# Top.net
KiCad netlist of a schematic drawn in Altium Designer
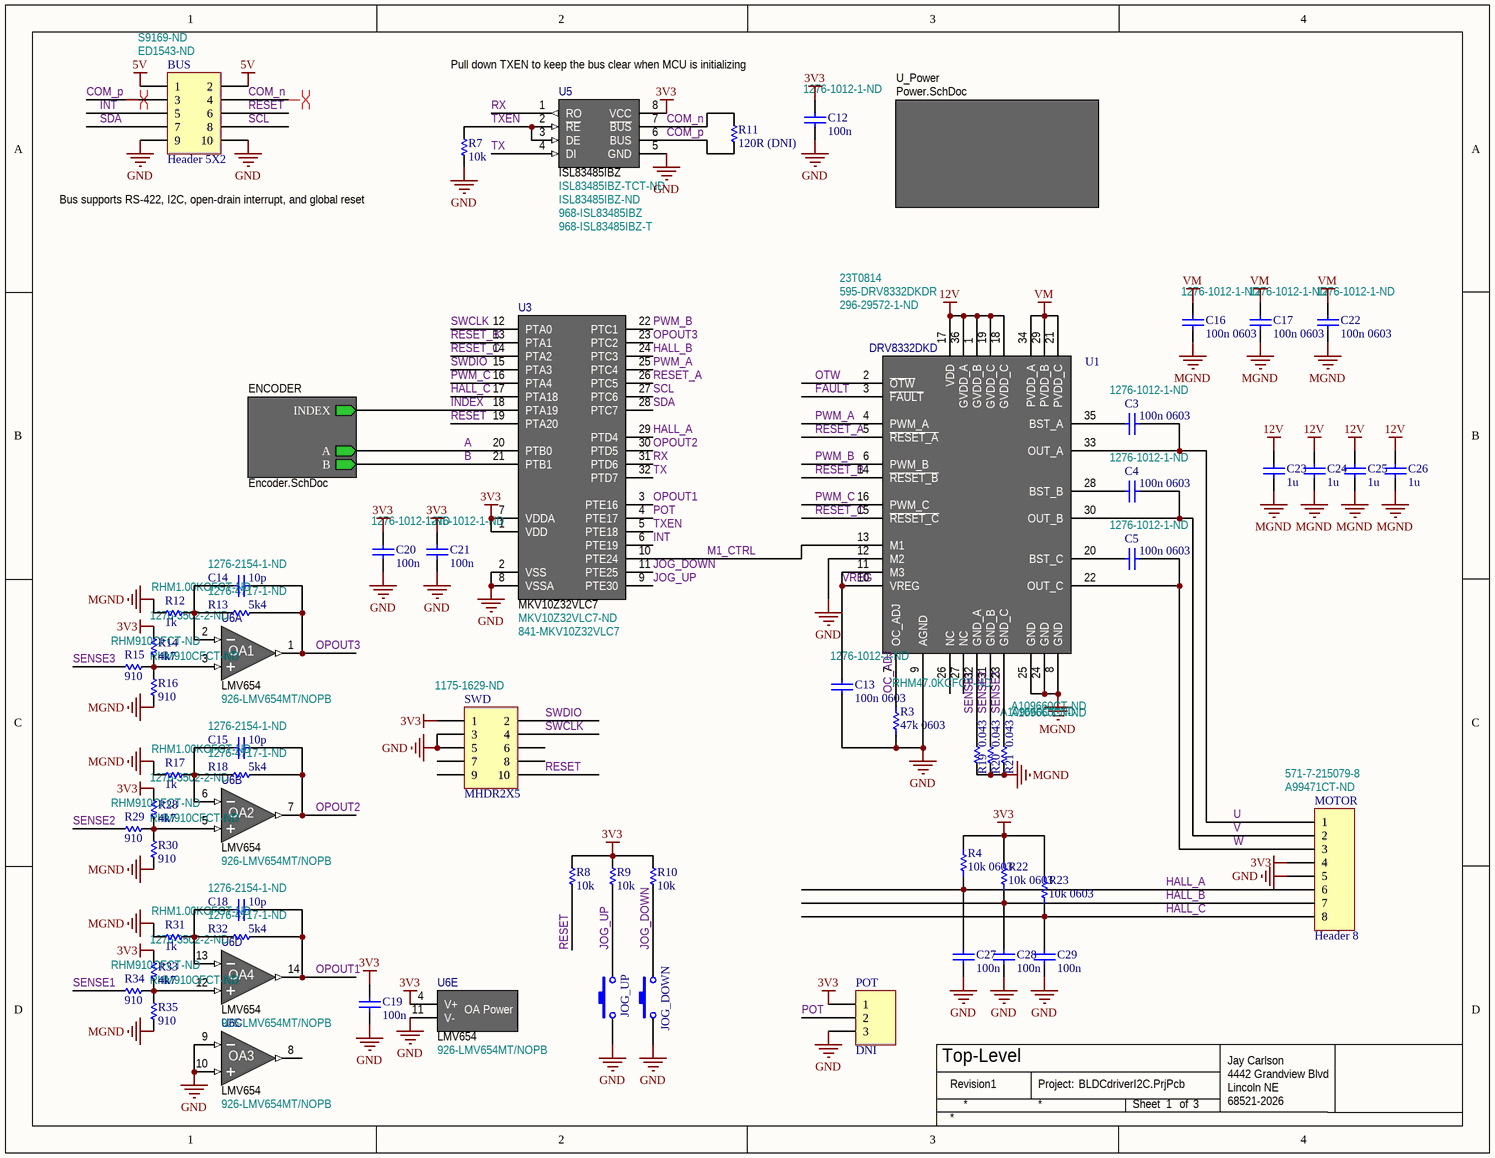
[diagram p0: Top.SchDoc]

(export (version "E")
  (design (tool "Eeschema 10.0.6"))
  (components
    (comp (ref "BUS")
      (value "Header 5X2")
      (footprint "HDR2X5_SHROUDED")
      (description "Header, 5-Pin, Dual row")
      (fields
        (field (name "SUPPLIER PART NUMBER 1") "ED1543-ND")
        (field (name "SUPPLIER PART NUMBER 2") "S9169-ND")
        (field (name "PUBLISHER") "Altium Limited")
      )
      (libsource (lib "Miscellaneous Connectors") (part "Header 5X2"))
    )
    (comp (ref "C3")
      (value "100n 0603")
      (footprint "CAPC1608N")
      (description "Capacitor")
      (fields
        (field (name "SUPPLIER PART NUMBER 1") "1276-1012-1-ND")
        (field (name "PUBLISHER") "Altium Limited")
      )
      (libsource (lib "Miscellaneous Devices") (part "Cap"))
    )
    (comp (ref "C4")
      (value "100n 0603")
      (footprint "CAPC1608N")
      (description "Capacitor")
      (fields
        (field (name "SUPPLIER PART NUMBER 1") "1276-1012-1-ND")
        (field (name "PUBLISHER") "Altium Limited")
      )
      (libsource (lib "Miscellaneous Devices") (part "Cap"))
    )
    (comp (ref "C5")
      (value "100n 0603")
      (footprint "CAPC1608N")
      (description "Capacitor")
      (fields
        (field (name "SUPPLIER PART NUMBER 1") "1276-1012-1-ND")
        (field (name "PUBLISHER") "Altium Limited")
      )
      (libsource (lib "Miscellaneous Devices") (part "Cap"))
    )
    (comp (ref "C12")
      (value "100n")
      (footprint "CAPC1608N")
      (description "Capacitor (Semiconductor SIM Model)")
      (fields
        (field (name "SUPPLIER PART NUMBER 1") "1276-1012-1-ND")
        (field (name "PUBLISHER") "Altium Limited")
      )
      (libsource (lib "Miscellaneous Devices") (part "Cap Semi"))
    )
    (comp (ref "C13")
      (value "100n 0603")
      (footprint "CAPC1608N")
      (description "Capacitor")
      (fields
        (field (name "SUPPLIER PART NUMBER 1") "1276-1012-1-ND")
        (field (name "PUBLISHER") "Altium Limited")
      )
      (libsource (lib "Miscellaneous Devices") (part "Cap"))
    )
    (comp (ref "C14")
      (value "10p")
      (footprint "CAPC1608N")
      (description "Capacitor (Semiconductor SIM Model)")
      (fields
        (field (name "SUPPLIER PART NUMBER 1") "1276-2154-1-ND")
        (field (name "PUBLISHER") "Altium Limited")
      )
      (libsource (lib "Miscellaneous Devices") (part "Cap Semi"))
    )
    (comp (ref "C15")
      (value "10p")
      (footprint "CAPC1608N")
      (description "Capacitor (Semiconductor SIM Model)")
      (fields
        (field (name "SUPPLIER PART NUMBER 1") "1276-2154-1-ND")
        (field (name "PUBLISHER") "Altium Limited")
      )
      (libsource (lib "Miscellaneous Devices") (part "Cap Semi"))
    )
    (comp (ref "C16")
      (value "100n 0603")
      (footprint "CAPC1608N")
      (description "Capacitor")
      (fields
        (field (name "SUPPLIER PART NUMBER 1") "1276-1012-1-ND")
        (field (name "PUBLISHER") "Altium Limited")
      )
      (libsource (lib "Miscellaneous Devices") (part "Cap"))
    )
    (comp (ref "C17")
      (value "100n 0603")
      (footprint "CAPC1608N")
      (description "Capacitor")
      (fields
        (field (name "SUPPLIER PART NUMBER 1") "1276-1012-1-ND")
        (field (name "PUBLISHER") "Altium Limited")
      )
      (libsource (lib "Miscellaneous Devices") (part "Cap"))
    )
    (comp (ref "C18")
      (value "10p")
      (footprint "CAPC1608N")
      (description "Capacitor (Semiconductor SIM Model)")
      (fields
        (field (name "SUPPLIER PART NUMBER 1") "1276-2154-1-ND")
        (field (name "PUBLISHER") "Altium Limited")
      )
      (libsource (lib "Miscellaneous Devices") (part "Cap Semi"))
    )
    (comp (ref "C19")
      (value "100n")
      (footprint "CAPC1608N")
      (description "Capacitor (Semiconductor SIM Model)")
      (fields (field (name "PUBLISHER") "Altium Limited"))
      (libsource (lib "Miscellaneous Devices") (part "Cap Semi"))
    )
    (comp (ref "C20")
      (value "100n")
      (footprint "CAPC1608N")
      (description "Capacitor (Semiconductor SIM Model)")
      (fields
        (field (name "SUPPLIER PART NUMBER 1") "1276-1012-1-ND")
        (field (name "PUBLISHER") "Altium Limited")
      )
      (libsource (lib "Miscellaneous Devices") (part "Cap Semi"))
    )
    (comp (ref "C21")
      (value "100n")
      (footprint "CAPC1608N")
      (description "Capacitor (Semiconductor SIM Model)")
      (fields
        (field (name "SUPPLIER PART NUMBER 1") "1276-1012-1-ND")
        (field (name "PUBLISHER") "Altium Limited")
      )
      (libsource (lib "Miscellaneous Devices") (part "Cap Semi"))
    )
    (comp (ref "C22")
      (value "100n 0603")
      (footprint "CAPC1608N")
      (description "Capacitor")
      (fields
        (field (name "SUPPLIER PART NUMBER 1") "1276-1012-1-ND")
        (field (name "PUBLISHER") "Altium Limited")
      )
      (libsource (lib "Miscellaneous Devices") (part "Cap"))
    )
    (comp (ref "C23")
      (value "1u")
      (footprint "CAPC1608N")
      (description "Capacitor (Semiconductor SIM Model)")
      (fields (field (name "PUBLISHER") "Altium Limited"))
      (libsource (lib "Miscellaneous Devices") (part "Cap Semi"))
    )
    (comp (ref "C24")
      (value "1u")
      (footprint "CAPC1608N")
      (description "Capacitor (Semiconductor SIM Model)")
      (fields (field (name "PUBLISHER") "Altium Limited"))
      (libsource (lib "Miscellaneous Devices") (part "Cap Semi"))
    )
    (comp (ref "C25")
      (value "1u")
      (footprint "CAPC1608N")
      (description "Capacitor (Semiconductor SIM Model)")
      (fields (field (name "PUBLISHER") "Altium Limited"))
      (libsource (lib "Miscellaneous Devices") (part "Cap Semi"))
    )
    (comp (ref "C26")
      (value "1u")
      (footprint "CAPC1608N")
      (description "Capacitor (Semiconductor SIM Model)")
      (fields (field (name "PUBLISHER") "Altium Limited"))
      (libsource (lib "Miscellaneous Devices") (part "Cap Semi"))
    )
    (comp (ref "C27")
      (value "100n")
      (footprint "CAPC1608N")
      (description "Capacitor (Semiconductor SIM Model)")
      (fields (field (name "PUBLISHER") "Altium Limited"))
      (libsource (lib "Miscellaneous Devices") (part "Cap Semi"))
    )
    (comp (ref "C28")
      (value "100n")
      (footprint "CAPC1608N")
      (description "Capacitor (Semiconductor SIM Model)")
      (fields (field (name "PUBLISHER") "Altium Limited"))
      (libsource (lib "Miscellaneous Devices") (part "Cap Semi"))
    )
    (comp (ref "C29")
      (value "100n")
      (footprint "CAPC1608N")
      (description "Capacitor (Semiconductor SIM Model)")
      (fields (field (name "PUBLISHER") "Altium Limited"))
      (libsource (lib "Miscellaneous Devices") (part "Cap Semi"))
    )
    (comp (ref "JOG_DOWN")
      (value "SW-PB")
      (footprint "SW/PB-SMD/H8")
      (description "Switch")
      (fields (field (name "PUBLISHER") "Altium Limited"))
      (libsource (lib "Miscellaneous Devices") (part "SW-PB"))
    )
    (comp (ref "JOG_UP")
      (value "SW-PB")
      (footprint "SW/PB-SMD/H8")
      (description "Switch")
      (fields (field (name "PUBLISHER") "Altium Limited"))
      (libsource (lib "Miscellaneous Devices") (part "SW-PB"))
    )
    (comp (ref "MOTOR")
      (value "Header 8")
      (footprint "7-215079-8")
      (description "Header, 8-Pin")
      (fields
        (field (name "SUPPLIER PART NUMBER 1") "A99471CT-ND")
        (field (name "SUPPLIER PART NUMBER 2") "571-7-215079-8")
        (field (name "PUBLISHER") "Altium Limited")
      )
      (libsource (lib "Miscellaneous Connectors") (part "Header 8"))
    )
    (comp (ref "POT")
      (value "DNI")
      (footprint "HDR1X3")
      (description "Header, 3-Pin")
      (fields (field (name "PUBLISHER") "Altium Limited"))
      (libsource (lib "Miscellaneous Connectors") (part "Header 3"))
    )
    (comp (ref "R3")
      (value "47k 0603")
      (footprint "RESC1608N")
      (description "Semiconductor Resistor")
      (fields
        (field (name "SUPPLIER PART NUMBER 1") "RHM47.0KCFCT-ND")
        (field (name "PUBLISHER") "Altium Limited")
      )
      (libsource (lib "") (part "Res Semi_1"))
    )
    (comp (ref "R4")
      (value "10k 0603")
      (footprint "RESC1608N")
      (description "Semiconductor Resistor")
      (fields (field (name "PUBLISHER") "Altium Limited"))
      (libsource (lib "") (part "Res Semi_1"))
    )
    (comp (ref "R7")
      (value "10k")
      (footprint "RESC1608N")
      (description "Semiconductor Resistor")
      (fields (field (name "PUBLISHER") "Altium Limited"))
      (libsource (lib "Miscellaneous Devices") (part "Res Semi"))
    )
    (comp (ref "R8")
      (value "10k")
      (footprint "RESC1608N")
      (description "Semiconductor Resistor")
      (fields (field (name "PUBLISHER") "Altium Limited"))
      (libsource (lib "Miscellaneous Devices") (part "Res Semi"))
    )
    (comp (ref "R9")
      (value "10k")
      (footprint "RESC1608N")
      (description "Semiconductor Resistor")
      (fields (field (name "PUBLISHER") "Altium Limited"))
      (libsource (lib "Miscellaneous Devices") (part "Res Semi"))
    )
    (comp (ref "R10")
      (value "10k")
      (footprint "RESC1608N")
      (description "Semiconductor Resistor")
      (fields (field (name "PUBLISHER") "Altium Limited"))
      (libsource (lib "Miscellaneous Devices") (part "Res Semi"))
    )
    (comp (ref "R11")
      (value "120R (DNI)")
      (footprint "RESC1608N")
      (description "Semiconductor Resistor")
      (fields (field (name "PUBLISHER") "Altium Limited"))
      (libsource (lib "Miscellaneous Devices") (part "Res Semi"))
    )
    (comp (ref "R12")
      (value "1k")
      (footprint "RESC1608N")
      (description "Semiconductor Resistor")
      (fields
        (field (name "SUPPLIER PART NUMBER 1") "RHM1.00KCFCT-ND")
        (field (name "PUBLISHER") "Altium Limited")
      )
      (libsource (lib "Miscellaneous Devices") (part "Res Semi"))
    )
    (comp (ref "R13")
      (value "5k4")
      (footprint "RESC1608N")
      (description "Semiconductor Resistor")
      (fields
        (field (name "SUPPLIER PART NUMBER 1") "1276-4717-1-ND")
        (field (name "PUBLISHER") "Altium Limited")
      )
      (libsource (lib "Miscellaneous Devices") (part "Res Semi"))
    )
    (comp (ref "R14")
      (value "4k7")
      (footprint "RESC1608N")
      (description "Semiconductor Resistor")
      (fields
        (field (name "SUPPLIER PART NUMBER 1") "1276-3502-2-ND")
        (field (name "PUBLISHER") "Altium Limited")
      )
      (libsource (lib "Miscellaneous Devices") (part "Res Semi"))
    )
    (comp (ref "R15")
      (value "910")
      (footprint "RESC1608N")
      (description "Semiconductor Resistor")
      (fields
        (field (name "SUPPLIER PART NUMBER 1") "RHM910CFCT-ND")
        (field (name "PUBLISHER") "Altium Limited")
      )
      (libsource (lib "Miscellaneous Devices") (part "Res Semi"))
    )
    (comp (ref "R16")
      (value "910")
      (footprint "RESC1608N")
      (description "Semiconductor Resistor")
      (fields
        (field (name "SUPPLIER PART NUMBER 1") "RHM910CFCT-ND")
        (field (name "PUBLISHER") "Altium Limited")
      )
      (libsource (lib "Miscellaneous Devices") (part "Res Semi"))
    )
    (comp (ref "R17")
      (value "1k")
      (footprint "RESC1608N")
      (description "Semiconductor Resistor")
      (fields
        (field (name "SUPPLIER PART NUMBER 1") "RHM1.00KCFCT-ND")
        (field (name "PUBLISHER") "Altium Limited")
      )
      (libsource (lib "Miscellaneous Devices") (part "Res Semi"))
    )
    (comp (ref "R18")
      (value "5k4")
      (footprint "RESC1608N")
      (description "Semiconductor Resistor")
      (fields
        (field (name "SUPPLIER PART NUMBER 1") "1276-4717-1-ND")
        (field (name "PUBLISHER") "Altium Limited")
      )
      (libsource (lib "Miscellaneous Devices") (part "Res Semi"))
    )
    (comp (ref "R19")
      (value "0.043")
      (footprint "RESC3216N")
      (description "Semiconductor Resistor")
      (fields
        (field (name "SUPPLIER PART NUMBER 1") "A109660CT-ND")
        (field (name "PUBLISHER") "Altium Limited")
      )
      (libsource (lib "Miscellaneous Devices") (part "Res Semi"))
    )
    (comp (ref "R20")
      (value "0.043")
      (footprint "RESC3216N")
      (description "Semiconductor Resistor")
      (fields
        (field (name "SUPPLIER PART NUMBER 1") "A109660CT-ND")
        (field (name "PUBLISHER") "Altium Limited")
      )
      (libsource (lib "Miscellaneous Devices") (part "Res Semi"))
    )
    (comp (ref "R21")
      (value "0.043")
      (footprint "RESC3216N")
      (description "Semiconductor Resistor")
      (fields
        (field (name "SUPPLIER PART NUMBER 1") "A109660CT-ND")
        (field (name "PUBLISHER") "Altium Limited")
      )
      (libsource (lib "Miscellaneous Devices") (part "Res Semi"))
    )
    (comp (ref "R22")
      (value "10k 0603")
      (footprint "RESC1608N")
      (description "Semiconductor Resistor")
      (fields (field (name "PUBLISHER") "Altium Limited"))
      (libsource (lib "") (part "Res Semi_1"))
    )
    (comp (ref "R23")
      (value "10k 0603")
      (footprint "RESC1608N")
      (description "Semiconductor Resistor")
      (fields (field (name "PUBLISHER") "Altium Limited"))
      (libsource (lib "") (part "Res Semi_1"))
    )
    (comp (ref "R28")
      (value "4k7")
      (footprint "RESC1608N")
      (description "Semiconductor Resistor")
      (fields
        (field (name "SUPPLIER PART NUMBER 1") "1276-3502-2-ND")
        (field (name "PUBLISHER") "Altium Limited")
      )
      (libsource (lib "Miscellaneous Devices") (part "Res Semi"))
    )
    (comp (ref "R29")
      (value "910")
      (footprint "RESC1608N")
      (description "Semiconductor Resistor")
      (fields
        (field (name "SUPPLIER PART NUMBER 1") "RHM910CFCT-ND")
        (field (name "PUBLISHER") "Altium Limited")
      )
      (libsource (lib "Miscellaneous Devices") (part "Res Semi"))
    )
    (comp (ref "R30")
      (value "910")
      (footprint "RESC1608N")
      (description "Semiconductor Resistor")
      (fields
        (field (name "SUPPLIER PART NUMBER 1") "RHM910CFCT-ND")
        (field (name "PUBLISHER") "Altium Limited")
      )
      (libsource (lib "Miscellaneous Devices") (part "Res Semi"))
    )
    (comp (ref "R31")
      (value "1k")
      (footprint "RESC1608N")
      (description "Semiconductor Resistor")
      (fields
        (field (name "SUPPLIER PART NUMBER 1") "RHM1.00KCFCT-ND")
        (field (name "PUBLISHER") "Altium Limited")
      )
      (libsource (lib "Miscellaneous Devices") (part "Res Semi"))
    )
    (comp (ref "R32")
      (value "5k4")
      (footprint "RESC1608N")
      (description "Semiconductor Resistor")
      (fields
        (field (name "SUPPLIER PART NUMBER 1") "1276-4717-1-ND")
        (field (name "PUBLISHER") "Altium Limited")
      )
      (libsource (lib "Miscellaneous Devices") (part "Res Semi"))
    )
    (comp (ref "R33")
      (value "4k7")
      (footprint "RESC1608N")
      (description "Semiconductor Resistor")
      (fields
        (field (name "SUPPLIER PART NUMBER 1") "1276-3502-2-ND")
        (field (name "PUBLISHER") "Altium Limited")
      )
      (libsource (lib "Miscellaneous Devices") (part "Res Semi"))
    )
    (comp (ref "R34")
      (value "910")
      (footprint "RESC1608N")
      (description "Semiconductor Resistor")
      (fields
        (field (name "SUPPLIER PART NUMBER 1") "RHM910CFCT-ND")
        (field (name "PUBLISHER") "Altium Limited")
      )
      (libsource (lib "Miscellaneous Devices") (part "Res Semi"))
    )
    (comp (ref "R35")
      (value "910")
      (footprint "RESC1608N")
      (description "Semiconductor Resistor")
      (fields
        (field (name "SUPPLIER PART NUMBER 1") "RHM910CFCT-ND")
        (field (name "PUBLISHER") "Altium Limited")
      )
      (libsource (lib "Miscellaneous Devices") (part "Res Semi"))
    )
    (comp (ref "SWD")
      (value "MHDR2X5")
      (footprint "MHDR2X5SMD_SHROUD")
      (description "Header, 5-Pin, Dual row")
      (fields
        (field (name "SUPPLIER PART NUMBER 1") "1175-1629-ND")
        (field (name "PUBLISHER") "Altium Limited")
      )
      (libsource (lib "Miscellaneous Connectors") (part "MHDR2X5"))
    )
    (comp (ref "U1")
      (value "DRV8332DKD")
      (footprint "DKD36")
      (fields
        (field (name "SUPPLIER PART NUMBER 1") "296-29572-1-ND")
        (field (name "SUPPLIER PART NUMBER 2") "595-DRV8332DKDR")
        (field (name "SUPPLIER PART NUMBER 3") "23T0814")
      )
      (libsource (lib "TI Motor Driver") (part "DRV8332DKD"))
    )
    (comp (ref "U3")
      (value "MKV10Z32VLC7")
      (footprint "QFP80P900X900-32N")
      (description "Kinetis Cortex-M0+75 MHz Motor Control")
      (fields
        (field (name "SUPPLIER PART NUMBER 1") "MKV10Z32VLC7-ND")
        (field (name "SUPPLIER PART NUMBER 2") "841-MKV10Z32VLC7")
      )
      (libsource (lib "Freescale K-Series ARM Microcontroller") (part "MKV10Z32VLC7"))
    )
    (comp (ref "U5")
      (value "ISL83485IBZ")
      (footprint "SOIC127P600-8N")
      (description "Half-duplex differential transceiver, 10 Mbps")
      (fields
        (field (name "SUPPLIER PART NUMBER 1") "ISL83485IBZ-TCT-ND")
        (field (name "SUPPLIER PART NUMBER 2") "ISL83485IBZ-ND")
        (field (name "SUPPLIER PART NUMBER 3") "968-ISL83485IBZ")
        (field (name "SUPPLIER PART NUMBER 4") "968-ISL83485IBZ-T")
      )
      (libsource (lib "Intersil Line Drivers") (part "ISL83485IBZ"))
    )
    (comp (ref "U6")
      (value "LMV654")
      (footprint "TSOP65P640-14AN")
      (description "12 MHz, Low Voltage, Low Power Amplifiers")
      (fields (field (name "SUPPLIER PART NUMBER 2") "926-LMV654MT/NOPB"))
      (libsource (lib "TI Operational Amplifier") (part "LMV654"))
    )
  )
  (nets
    (net (code "1") (name "/A") (class "Default")
      (node (ref "U3") (pin "20") (pinfunction "PTB0_20") (pintype "passive"))
    )
    (net (code "2") (name "/B") (class "Default")
      (node (ref "U3") (pin "21") (pinfunction "PTB1_21") (pintype "passive"))
    )
    (net (code "3") (name "/COM_n") (class "Default")
      (node (ref "BUS") (pin "4") (pinfunction "4_4") (pintype "passive"))
      (node (ref "R11") (pin "2") (pinfunction "2_2") (pintype "passive"))
      (node (ref "U5") (pin "7") (pinfunction "~{BUS}_7") (pintype "power_in"))
    )
    (net (code "4") (name "/COM_p") (class "Default")
      (node (ref "BUS") (pin "3") (pinfunction "3_3") (pintype "passive"))
      (node (ref "R11") (pin "1") (pinfunction "1_1") (pintype "passive"))
      (node (ref "U5") (pin "6") (pinfunction "BUS_6") (pintype "power_in"))
    )
    (net (code "5") (name "/FAULT") (class "Default")
      (node (ref "U1") (pin "3") (pinfunction "~{FAULT}_3") (pintype "passive"))
    )
    (net (code "6") (name "/HALL_A") (class "Default")
      (node (ref "C27") (pin "2") (pinfunction "2_2") (pintype "passive"))
      (node (ref "MOTOR") (pin "6") (pinfunction "6_6") (pintype "passive"))
      (node (ref "R4") (pin "2") (pinfunction "2_2") (pintype "passive"))
      (node (ref "U3") (pin "29") (pinfunction "PTD4_29") (pintype "passive"))
    )
    (net (code "7") (name "/HALL_B") (class "Default")
      (node (ref "C28") (pin "2") (pinfunction "2_2") (pintype "passive"))
      (node (ref "MOTOR") (pin "7") (pinfunction "7_7") (pintype "passive"))
      (node (ref "R22") (pin "2") (pinfunction "2_2") (pintype "passive"))
      (node (ref "U3") (pin "24") (pinfunction "PTC3_24") (pintype "passive"))
    )
    (net (code "8") (name "/HALL_C") (class "Default")
      (node (ref "C29") (pin "2") (pinfunction "2_2") (pintype "passive"))
      (node (ref "MOTOR") (pin "8") (pinfunction "8_8") (pintype "passive"))
      (node (ref "R23") (pin "2") (pinfunction "2_2") (pintype "passive"))
      (node (ref "U3") (pin "17") (pinfunction "PTA18_17") (pintype "passive"))
    )
    (net (code "9") (name "/INDEX") (class "Default")
      (node (ref "U3") (pin "18") (pinfunction "PTA19_18") (pintype "passive"))
    )
    (net (code "10") (name "/INT") (class "Default")
      (node (ref "BUS") (pin "5") (pinfunction "5_5") (pintype "passive"))
      (node (ref "U3") (pin "6") (pinfunction "PTE19_6") (pintype "passive"))
    )
    (net (code "11") (name "/JOG_DOWN") (class "Default")
      (node (ref "JOG_DOWN") (pin "2") (pinfunction "2_2") (pintype "passive"))
      (node (ref "R10") (pin "1") (pinfunction "1_1") (pintype "passive"))
      (node (ref "U3") (pin "11") (pinfunction "PTE25_11") (pintype "passive"))
    )
    (net (code "12") (name "/JOG_UP") (class "Default")
      (node (ref "JOG_UP") (pin "2") (pinfunction "2_2") (pintype "passive"))
      (node (ref "R9") (pin "1") (pinfunction "1_1") (pintype "passive"))
      (node (ref "U3") (pin "9") (pinfunction "PTE30_9") (pintype "passive"))
    )
    (net (code "13") (name "/M1_CTRL") (class "Default")
      (node (ref "U1") (pin "13") (pinfunction "M1_13") (pintype "passive"))
      (node (ref "U3") (pin "10") (pinfunction "PTE24_10") (pintype "passive"))
    )
    (net (code "14") (name "/OC_ADJ") (class "Default")
      (node (ref "R3") (pin "1") (pinfunction "1_1") (pintype "passive"))
      (node (ref "U1") (pin "7") (pinfunction "OC_ADJ_7") (pintype "passive"))
    )
    (net (code "15") (name "/OPOUT1") (class "Default")
      (node (ref "C18") (pin "2") (pinfunction "2_2") (pintype "passive"))
      (node (ref "R32") (pin "2") (pinfunction "2_2") (pintype "passive"))
      (node (ref "U3") (pin "3") (pinfunction "PTE16_3") (pintype "passive"))
      (node (ref "U6") (pin "14") (pinfunction "OUT_D_14") (pintype "output"))
    )
    (net (code "16") (name "/OPOUT2") (class "Default")
      (node (ref "C15") (pin "2") (pinfunction "2_2") (pintype "passive"))
      (node (ref "R18") (pin "2") (pinfunction "2_2") (pintype "passive"))
      (node (ref "U3") (pin "30") (pinfunction "PTD5_30") (pintype "passive"))
      (node (ref "U6") (pin "7") (pinfunction "OUT_B_7") (pintype "output"))
    )
    (net (code "17") (name "/OPOUT3") (class "Default")
      (node (ref "C14") (pin "2") (pinfunction "2_2") (pintype "passive"))
      (node (ref "R13") (pin "2") (pinfunction "2_2") (pintype "passive"))
      (node (ref "U3") (pin "23") (pinfunction "PTC2_23") (pintype "passive"))
      (node (ref "U6") (pin "1") (pinfunction "OUT_A_1") (pintype "output"))
    )
    (net (code "18") (name "/OTW") (class "Default")
      (node (ref "U1") (pin "2") (pinfunction "~{OTW}_2") (pintype "passive"))
    )
    (net (code "19") (name "/POT") (class "Default")
      (node (ref "POT") (pin "2") (pinfunction "2_2") (pintype "passive"))
      (node (ref "U3") (pin "4") (pinfunction "PTE17_4") (pintype "passive"))
    )
    (net (code "20") (name "/PWM_A") (class "Default")
      (node (ref "U1") (pin "4") (pinfunction "PWM_A_4") (pintype "passive"))
      (node (ref "U3") (pin "25") (pinfunction "PTC4_25") (pintype "passive"))
    )
    (net (code "21") (name "/PWM_B") (class "Default")
      (node (ref "U1") (pin "6") (pinfunction "PWM_B_6") (pintype "passive"))
      (node (ref "U3") (pin "22") (pinfunction "PTC1_22") (pintype "passive"))
    )
    (net (code "22") (name "/PWM_C") (class "Default")
      (node (ref "U1") (pin "16") (pinfunction "PWM_C_16") (pintype "passive"))
      (node (ref "U3") (pin "16") (pinfunction "PTA4_16") (pintype "passive"))
    )
    (net (code "23") (name "/RESET") (class "Default")
      (node (ref "BUS") (pin "6") (pinfunction "6_6") (pintype "passive"))
      (node (ref "R8") (pin "1") (pinfunction "1_1") (pintype "passive"))
      (node (ref "SWD") (pin "10") (pinfunction "10_10") (pintype "passive"))
      (node (ref "U3") (pin "19") (pinfunction "PTA20_19") (pintype "passive"))
    )
    (net (code "24") (name "/RESET_A") (class "Default")
      (node (ref "U1") (pin "5") (pinfunction "~{RESET_A}_5") (pintype "passive"))
      (node (ref "U3") (pin "26") (pinfunction "PTC5_26") (pintype "passive"))
    )
    (net (code "25") (name "/RESET_B") (class "Default")
      (node (ref "U1") (pin "14") (pinfunction "~{RESET_B}_14") (pintype "passive"))
      (node (ref "U3") (pin "13") (pinfunction "PTA1_13") (pintype "passive"))
    )
    (net (code "26") (name "/RESET_C") (class "Default")
      (node (ref "U1") (pin "15") (pinfunction "~{RESET_C}_15") (pintype "passive"))
      (node (ref "U3") (pin "14") (pinfunction "PTA2_14") (pintype "passive"))
    )
    (net (code "27") (name "/RX") (class "Default")
      (node (ref "U3") (pin "31") (pinfunction "PTD6_31") (pintype "passive"))
      (node (ref "U5") (pin "1") (pinfunction "RO_1") (pintype "output"))
    )
    (net (code "28") (name "/SCL") (class "Default")
      (node (ref "BUS") (pin "8") (pinfunction "8_8") (pintype "passive"))
      (node (ref "U3") (pin "27") (pinfunction "PTC6_27") (pintype "passive"))
    )
    (net (code "29") (name "/SDA") (class "Default")
      (node (ref "BUS") (pin "7") (pinfunction "7_7") (pintype "passive"))
      (node (ref "U3") (pin "28") (pinfunction "PTC7_28") (pintype "passive"))
    )
    (net (code "30") (name "/SENSE1") (class "Default")
      (node (ref "R19") (pin "2") (pinfunction "2_2") (pintype "passive"))
      (node (ref "R34") (pin "1") (pinfunction "1_1") (pintype "passive"))
      (node (ref "U1") (pin "32") (pinfunction "GND_A_32") (pintype "passive"))
    )
    (net (code "31") (name "/SENSE2") (class "Default")
      (node (ref "R20") (pin "2") (pinfunction "2_2") (pintype "passive"))
      (node (ref "R29") (pin "1") (pinfunction "1_1") (pintype "passive"))
      (node (ref "U1") (pin "31") (pinfunction "GND_B_31") (pintype "passive"))
    )
    (net (code "32") (name "/SENSE3") (class "Default")
      (node (ref "R15") (pin "1") (pinfunction "1_1") (pintype "passive"))
      (node (ref "R21") (pin "2") (pinfunction "2_2") (pintype "passive"))
      (node (ref "U1") (pin "23") (pinfunction "GND_C_23") (pintype "passive"))
    )
    (net (code "33") (name "/SWCLK") (class "Default")
      (node (ref "SWD") (pin "4") (pinfunction "4_4") (pintype "passive"))
      (node (ref "U3") (pin "12") (pinfunction "PTA0_12") (pintype "passive"))
    )
    (net (code "34") (name "/SWDIO") (class "Default")
      (node (ref "SWD") (pin "2") (pinfunction "2_2") (pintype "passive"))
      (node (ref "U3") (pin "15") (pinfunction "PTA3_15") (pintype "passive"))
    )
    (net (code "35") (name "/TX") (class "Default")
      (node (ref "U3") (pin "32") (pinfunction "PTD7_32") (pintype "passive"))
      (node (ref "U5") (pin "4") (pinfunction "DI_4") (pintype "input"))
    )
    (net (code "36") (name "/TXEN") (class "Default")
      (node (ref "R7") (pin "2") (pinfunction "2_2") (pintype "passive"))
      (node (ref "U3") (pin "5") (pinfunction "PTE18_5") (pintype "passive"))
      (node (ref "U5") (pin "2") (pinfunction "~{RE}_2") (pintype "input"))
      (node (ref "U5") (pin "3") (pinfunction "DE_3") (pintype "input"))
    )
    (net (code "37") (name "/U") (class "Default")
      (node (ref "C3") (pin "1") (pinfunction "1_1") (pintype "passive"))
      (node (ref "MOTOR") (pin "1") (pinfunction "1_1") (pintype "passive"))
      (node (ref "U1") (pin "33") (pinfunction "OUT_A_33") (pintype "passive"))
    )
    (net (code "38") (name "/V") (class "Default")
      (node (ref "C4") (pin "1") (pinfunction "1_1") (pintype "passive"))
      (node (ref "MOTOR") (pin "2") (pinfunction "2_2") (pintype "passive"))
      (node (ref "U1") (pin "30") (pinfunction "OUT_B_30") (pintype "passive"))
    )
    (net (code "39") (name "/VREG") (class "Default")
      (node (ref "C13") (pin "1") (pinfunction "1_1") (pintype "passive"))
      (node (ref "U1") (pin "10") (pinfunction "VREG_10") (pintype "passive"))
      (node (ref "U1") (pin "11") (pinfunction "M3_11") (pintype "passive"))
    )
    (net (code "40") (name "/W") (class "Default")
      (node (ref "C5") (pin "1") (pinfunction "1_1") (pintype "passive"))
      (node (ref "MOTOR") (pin "3") (pinfunction "3_3") (pintype "passive"))
      (node (ref "U1") (pin "22") (pinfunction "OUT_C_22") (pintype "passive"))
    )
    (net (code "41") (name "3V3") (class "Default")
      (node (ref "C12") (pin "2") (pinfunction "2_2") (pintype "passive"))
      (node (ref "C19") (pin "2") (pinfunction "2_2") (pintype "passive"))
      (node (ref "C20") (pin "2") (pinfunction "2_2") (pintype "passive"))
      (node (ref "C21") (pin "2") (pinfunction "2_2") (pintype "passive"))
      (node (ref "MOTOR") (pin "4") (pinfunction "4_4") (pintype "passive"))
      (node (ref "POT") (pin "1") (pinfunction "1_1") (pintype "passive"))
      (node (ref "R10") (pin "2") (pinfunction "2_2") (pintype "passive"))
      (node (ref "R14") (pin "2") (pinfunction "2_2") (pintype "passive"))
      (node (ref "R22") (pin "1") (pinfunction "1_1") (pintype "passive"))
      (node (ref "R23") (pin "1") (pinfunction "1_1") (pintype "passive"))
      (node (ref "R28") (pin "2") (pinfunction "2_2") (pintype "passive"))
      (node (ref "R33") (pin "2") (pinfunction "2_2") (pintype "passive"))
      (node (ref "R4") (pin "1") (pinfunction "1_1") (pintype "passive"))
      (node (ref "R8") (pin "2") (pinfunction "2_2") (pintype "passive"))
      (node (ref "R9") (pin "2") (pinfunction "2_2") (pintype "passive"))
      (node (ref "SWD") (pin "1") (pinfunction "1_1") (pintype "passive"))
      (node (ref "U3") (pin "1") (pinfunction "VDD_1") (pintype "passive"))
      (node (ref "U3") (pin "7") (pinfunction "VDDA_7") (pintype "passive"))
      (node (ref "U5") (pin "8") (pinfunction "VCC_8") (pintype "power_in"))
      (node (ref "U6") (pin "4") (pinfunction "V+_4") (pintype "power_in"))
    )
    (net (code "42") (name "5V") (class "Default")
      (node (ref "BUS") (pin "1") (pinfunction "1_1") (pintype "passive"))
      (node (ref "BUS") (pin "2") (pinfunction "2_2") (pintype "passive"))
    )
    (net (code "43") (name "12V") (class "Default")
      (node (ref "C23") (pin "2") (pinfunction "2_2") (pintype "passive"))
      (node (ref "C24") (pin "2") (pinfunction "2_2") (pintype "passive"))
      (node (ref "C25") (pin "2") (pinfunction "2_2") (pintype "passive"))
      (node (ref "C26") (pin "2") (pinfunction "2_2") (pintype "passive"))
      (node (ref "U1") (pin "1") (pinfunction "GVDD_B_1") (pintype "passive"))
      (node (ref "U1") (pin "17") (pinfunction "VDD_17") (pintype "passive"))
      (node (ref "U1") (pin "18") (pinfunction "GVDD_C_18") (pintype "passive"))
      (node (ref "U1") (pin "19") (pinfunction "GVDD_C_19") (pintype "passive"))
      (node (ref "U1") (pin "36") (pinfunction "GVDD_A_36") (pintype "passive"))
    )
    (net (code "44") (name "GND") (class "Default")
      (node (ref "BUS") (pin "10") (pinfunction "10_10") (pintype "passive"))
      (node (ref "BUS") (pin "9") (pinfunction "9_9") (pintype "passive"))
      (node (ref "C12") (pin "1") (pinfunction "1_1") (pintype "passive"))
      (node (ref "C13") (pin "2") (pinfunction "2_2") (pintype "passive"))
      (node (ref "C19") (pin "1") (pinfunction "1_1") (pintype "passive"))
      (node (ref "C20") (pin "1") (pinfunction "1_1") (pintype "passive"))
      (node (ref "C21") (pin "1") (pinfunction "1_1") (pintype "passive"))
      (node (ref "C27") (pin "1") (pinfunction "1_1") (pintype "passive"))
      (node (ref "C28") (pin "1") (pinfunction "1_1") (pintype "passive"))
      (node (ref "C29") (pin "1") (pinfunction "1_1") (pintype "passive"))
      (node (ref "JOG_DOWN") (pin "1") (pinfunction "1_1") (pintype "passive"))
      (node (ref "JOG_UP") (pin "1") (pinfunction "1_1") (pintype "passive"))
      (node (ref "MOTOR") (pin "5") (pinfunction "5_5") (pintype "passive"))
      (node (ref "POT") (pin "3") (pinfunction "3_3") (pintype "passive"))
      (node (ref "R3") (pin "2") (pinfunction "2_2") (pintype "passive"))
      (node (ref "R7") (pin "1") (pinfunction "1_1") (pintype "passive"))
      (node (ref "SWD") (pin "3") (pinfunction "3_3") (pintype "passive"))
      (node (ref "SWD") (pin "5") (pinfunction "5_5") (pintype "passive"))
      (node (ref "U1") (pin "12") (pinfunction "M2_12") (pintype "passive"))
      (node (ref "U1") (pin "9") (pinfunction "AGND_9") (pintype "passive"))
      (node (ref "U3") (pin "2") (pinfunction "VSS_2") (pintype "passive"))
      (node (ref "U3") (pin "8") (pinfunction "VSSA_8") (pintype "passive"))
      (node (ref "U5") (pin "5") (pinfunction "GND_5") (pintype "power_in"))
      (node (ref "U6") (pin "10") (pinfunction "IN_C+_10") (pintype "input"))
      (node (ref "U6") (pin "11") (pinfunction "V-_11") (pintype "power_in"))
      (node (ref "U6") (pin "9") (pinfunction "IN_C-_9") (pintype "input"))
    )
    (net (code "45") (name "MGND") (class "Default")
      (node (ref "C16") (pin "2") (pinfunction "2_2") (pintype "passive"))
      (node (ref "C17") (pin "2") (pinfunction "2_2") (pintype "passive"))
      (node (ref "C22") (pin "2") (pinfunction "2_2") (pintype "passive"))
      (node (ref "C23") (pin "1") (pinfunction "1_1") (pintype "passive"))
      (node (ref "C24") (pin "1") (pinfunction "1_1") (pintype "passive"))
      (node (ref "C25") (pin "1") (pinfunction "1_1") (pintype "passive"))
      (node (ref "C26") (pin "1") (pinfunction "1_1") (pintype "passive"))
      (node (ref "R12") (pin "1") (pinfunction "1_1") (pintype "passive"))
      (node (ref "R16") (pin "1") (pinfunction "1_1") (pintype "passive"))
      (node (ref "R17") (pin "1") (pinfunction "1_1") (pintype "passive"))
      (node (ref "R19") (pin "1") (pinfunction "1_1") (pintype "passive"))
      (node (ref "R20") (pin "1") (pinfunction "1_1") (pintype "passive"))
      (node (ref "R21") (pin "1") (pinfunction "1_1") (pintype "passive"))
      (node (ref "R30") (pin "1") (pinfunction "1_1") (pintype "passive"))
      (node (ref "R31") (pin "1") (pinfunction "1_1") (pintype "passive"))
      (node (ref "R35") (pin "1") (pinfunction "1_1") (pintype "passive"))
      (node (ref "U1") (pin "24") (pinfunction "GND_24") (pintype "passive"))
      (node (ref "U1") (pin "25") (pinfunction "GND_25") (pintype "passive"))
      (node (ref "U1") (pin "8") (pinfunction "GND_8") (pintype "passive"))
    )
    (net (code "46") (name "Net-(U1-BST_A)") (class "Default")
      (node (ref "C3") (pin "2") (pinfunction "2_2") (pintype "passive"))
      (node (ref "U1") (pin "35") (pinfunction "BST_A_35") (pintype "passive"))
    )
    (net (code "47") (name "Net-(U1-BST_B)") (class "Default")
      (node (ref "C4") (pin "2") (pinfunction "2_2") (pintype "passive"))
      (node (ref "U1") (pin "28") (pinfunction "BST_B_28") (pintype "passive"))
    )
    (net (code "48") (name "Net-(U1-BST_C)") (class "Default")
      (node (ref "C5") (pin "2") (pinfunction "2_2") (pintype "passive"))
      (node (ref "U1") (pin "20") (pinfunction "BST_C_20") (pintype "passive"))
    )
    (net (code "49") (name "Net-(U6A-IN_A+)") (class "Default")
      (node (ref "R14") (pin "1") (pinfunction "1_1") (pintype "passive"))
      (node (ref "R15") (pin "2") (pinfunction "2_2") (pintype "passive"))
      (node (ref "R16") (pin "2") (pinfunction "2_2") (pintype "passive"))
      (node (ref "U6") (pin "3") (pinfunction "IN_A+_3") (pintype "input"))
    )
    (net (code "50") (name "Net-(U6A-IN_A-)") (class "Default")
      (node (ref "C14") (pin "1") (pinfunction "1_1") (pintype "passive"))
      (node (ref "R12") (pin "2") (pinfunction "2_2") (pintype "passive"))
      (node (ref "R13") (pin "1") (pinfunction "1_1") (pintype "passive"))
      (node (ref "U6") (pin "2") (pinfunction "IN_A-_2") (pintype "input"))
    )
    (net (code "51") (name "Net-(U6B-IN_B+)") (class "Default")
      (node (ref "R28") (pin "1") (pinfunction "1_1") (pintype "passive"))
      (node (ref "R29") (pin "2") (pinfunction "2_2") (pintype "passive"))
      (node (ref "R30") (pin "2") (pinfunction "2_2") (pintype "passive"))
      (node (ref "U6") (pin "5") (pinfunction "IN_B+_5") (pintype "input"))
    )
    (net (code "52") (name "Net-(U6B-IN_B-)") (class "Default")
      (node (ref "C15") (pin "1") (pinfunction "1_1") (pintype "passive"))
      (node (ref "R17") (pin "2") (pinfunction "2_2") (pintype "passive"))
      (node (ref "R18") (pin "1") (pinfunction "1_1") (pintype "passive"))
      (node (ref "U6") (pin "6") (pinfunction "IN_B-_6") (pintype "input"))
    )
    (net (code "53") (name "Net-(U6D-IN_D+)") (class "Default")
      (node (ref "R33") (pin "1") (pinfunction "1_1") (pintype "passive"))
      (node (ref "R34") (pin "2") (pinfunction "2_2") (pintype "passive"))
      (node (ref "R35") (pin "2") (pinfunction "2_2") (pintype "passive"))
      (node (ref "U6") (pin "12") (pinfunction "IN_D+_12") (pintype "input"))
    )
    (net (code "54") (name "Net-(U6D-IN_D-)") (class "Default")
      (node (ref "C18") (pin "1") (pinfunction "1_1") (pintype "passive"))
      (node (ref "R31") (pin "2") (pinfunction "2_2") (pintype "passive"))
      (node (ref "R32") (pin "1") (pinfunction "1_1") (pintype "passive"))
      (node (ref "U6") (pin "13") (pinfunction "IN_D-_13") (pintype "input"))
    )
    (net (code "55") (name "VM") (class "Default")
      (node (ref "C16") (pin "1") (pinfunction "1_1") (pintype "passive"))
      (node (ref "C17") (pin "1") (pinfunction "1_1") (pintype "passive"))
      (node (ref "C22") (pin "1") (pinfunction "1_1") (pintype "passive"))
      (node (ref "U1") (pin "21") (pinfunction "PVDD_C_21") (pintype "passive"))
      (node (ref "U1") (pin "29") (pinfunction "PVDD_B_29") (pintype "passive"))
      (node (ref "U1") (pin "34") (pinfunction "PVDD_A_34") (pintype "passive"))
    )
    (net (code "56") (name "unconnected-(SWD-Pad6)") (class "Default")
      (node (ref "SWD") (pin "6") (pinfunction "6_6") (pintype "passive"))
    )
    (net (code "57") (name "unconnected-(SWD-Pad7)") (class "Default")
      (node (ref "SWD") (pin "7") (pinfunction "7_7") (pintype "passive"))
    )
    (net (code "58") (name "unconnected-(SWD-Pad8)") (class "Default")
      (node (ref "SWD") (pin "8") (pinfunction "8_8") (pintype "passive"))
    )
    (net (code "59") (name "unconnected-(SWD-Pad9)") (class "Default")
      (node (ref "SWD") (pin "9") (pinfunction "9_9") (pintype "passive"))
    )
    (net (code "60") (name "unconnected-(U1-NC-Pad26)") (class "Default")
      (node (ref "U1") (pin "26") (pinfunction "NC_26") (pintype "passive"))
    )
    (net (code "61") (name "unconnected-(U1-NC-Pad27)") (class "Default")
      (node (ref "U1") (pin "27") (pinfunction "NC_27") (pintype "passive"))
    )
    (net (code "62") (name "unconnected-(U6C-OUT_C-Pad8)") (class "Default")
      (node (ref "U6") (pin "8") (pinfunction "OUT_C_8") (pintype "output"))
    )
  )
)
